# RPi-Display_Bplus_v11.net
KiCad netlist of a schematic drawn in EAGLE
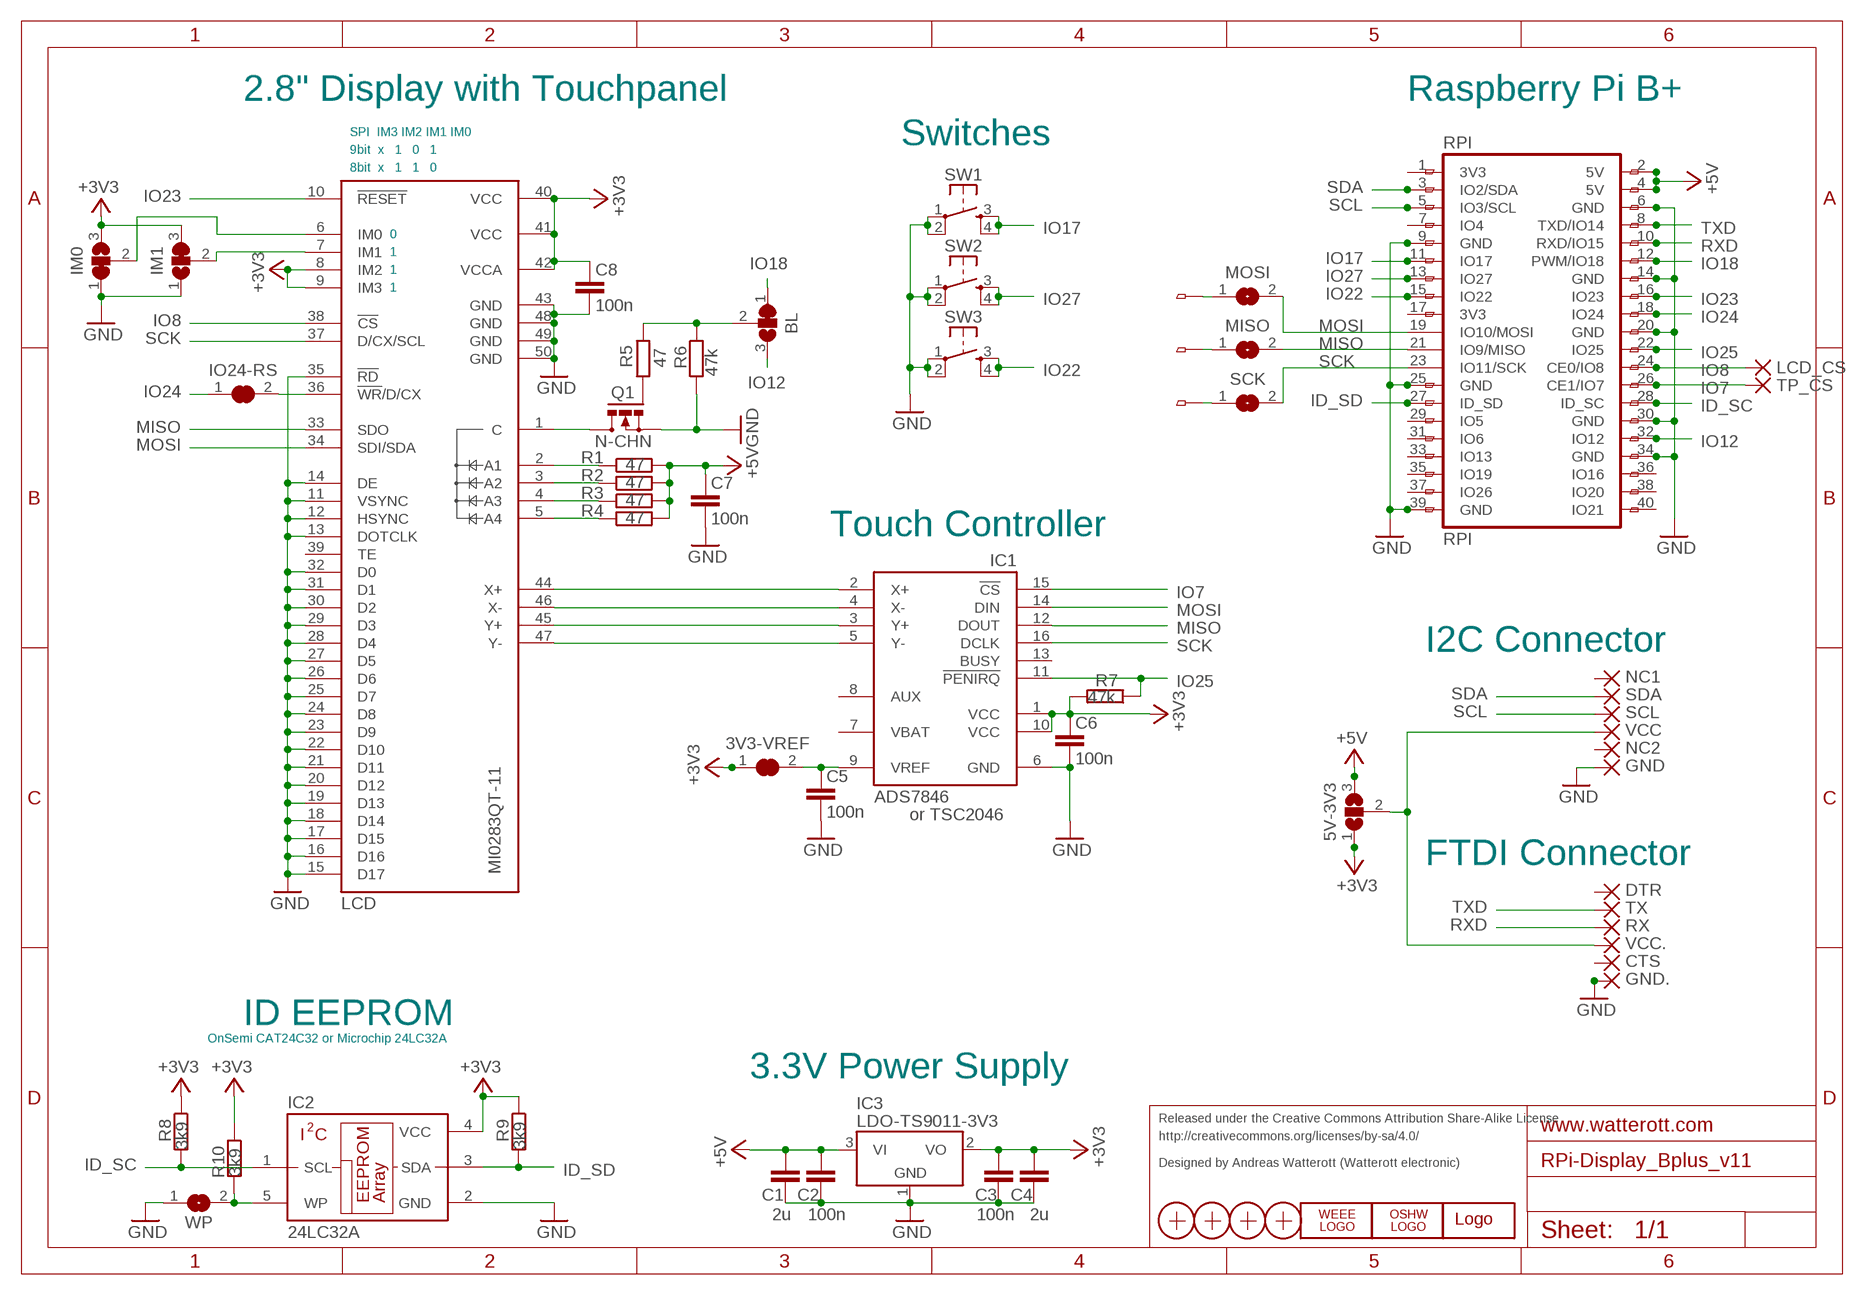
[diagram p0: schematic, sheet 1]

(export (version "E")
  (design (tool "Eeschema 10.0.6"))
  (components
    (comp (ref "3V3-VREF")
      (value "JUMPER2-NOCREAM")
      (footprint "eagle-import:JUMPER2_NC")
      (libsource (lib "eagle-import") (part "JUMPER2-NOCREAM"))
    )
    (comp (ref "5V-3V3")
      (value "JUMPER3-NOCREAM")
      (footprint "eagle-import:JUMPER3_NC")
      (libsource (lib "eagle-import") (part "JUMPER3-NOCREAM"))
    )
    (comp (ref "BL")
      (value "JUMPER3-NOCREAM")
      (footprint "eagle-import:JUMPER3_NC")
      (libsource (lib "eagle-import") (part "JUMPER3-NOCREAM"))
    )
    (comp (ref "C1")
      (value "2u")
      (footprint "eagle-import:C0603")
      (libsource (lib "eagle-import") (part "C-EUC0603"))
    )
    (comp (ref "C2")
      (value "100n")
      (footprint "eagle-import:C0603")
      (libsource (lib "eagle-import") (part "C-EUC0603"))
    )
    (comp (ref "C3")
      (value "100n")
      (footprint "eagle-import:C0603")
      (libsource (lib "eagle-import") (part "C-EUC0603"))
    )
    (comp (ref "C4")
      (value "2u")
      (footprint "eagle-import:C0603")
      (libsource (lib "eagle-import") (part "C-EUC0603"))
    )
    (comp (ref "C5")
      (value "100n")
      (footprint "eagle-import:C0603")
      (libsource (lib "eagle-import") (part "C-EUC0603"))
    )
    (comp (ref "C6")
      (value "100n")
      (footprint "eagle-import:C0603")
      (libsource (lib "eagle-import") (part "C-EUC0603"))
    )
    (comp (ref "C7")
      (value "100n")
      (footprint "eagle-import:C0603")
      (libsource (lib "eagle-import") (part "C-EUC0603"))
    )
    (comp (ref "C8")
      (value "100n")
      (footprint "eagle-import:C0603")
      (libsource (lib "eagle-import") (part "C-EUC0603"))
    )
    (comp (ref "CTS")
      (value "PAD-1.27X2.54_NC")
      (footprint "eagle-import:PAD-1.27X2.54_NC")
      (libsource (lib "eagle-import") (part "PAD-1.27X2.54_NC"))
    )
    (comp (ref "DTR")
      (value "PAD-1.27X2.54_NC")
      (footprint "eagle-import:PAD-1.27X2.54_NC")
      (libsource (lib "eagle-import") (part "PAD-1.27X2.54_NC"))
    )
    (comp (ref "GND")
      (value "PAD-1.27X2.54_NC")
      (footprint "eagle-import:PAD-1.27X2.54_NC")
      (libsource (lib "eagle-import") (part "PAD-1.27X2.54_NC"))
    )
    (comp (ref "GND.")
      (value "PAD-1.27X2.54_NC")
      (footprint "eagle-import:PAD-1.27X2.54_NC")
      (libsource (lib "eagle-import") (part "PAD-1.27X2.54_NC"))
    )
    (comp (ref "GPIO")
      (value "FH12-40S-0.5SH")
      (footprint "eagle-import:FH12-40S-0.5SH")
      (fields (field (name "MPN") "FH12-40S-0.5SH(55)"))
      (libsource (lib "eagle-import") (part "FH12-40S-0.5SH"))
    )
    (comp (ref "IC1")
      (value "ADS7846")
      (footprint "eagle-import:SSOP16")
      (libsource (lib "eagle-import") (part "ADS7846"))
    )
    (comp (ref "IC2")
      (value "24LC32A")
      (footprint "eagle-import:SOT23-5")
      (libsource (lib "eagle-import") (part "I2C_EEPROM-CAT24AA0X"))
    )
    (comp (ref "IC3")
      (value "LDO-TS9011-3V3")
      (footprint "eagle-import:SOT23")
      (libsource (lib "eagle-import") (part "LDO-TS9011-3V3"))
    )
    (comp (ref "IM0")
      (value "JUMPER3-NOCREAM")
      (footprint "eagle-import:JUMPER3_NC")
      (libsource (lib "eagle-import") (part "JUMPER3-NOCREAM"))
    )
    (comp (ref "IM1")
      (value "JUMPER3-NOCREAM")
      (footprint "eagle-import:JUMPER3_NC")
      (libsource (lib "eagle-import") (part "JUMPER3-NOCREAM"))
    )
    (comp (ref "IO24-RS")
      (value "JUMPER2-NOCREAM")
      (footprint "eagle-import:JUMPER2_NC")
      (libsource (lib "eagle-import") (part "JUMPER2-NOCREAM"))
    )
    (comp (ref "LCD")
      (value "MI0283QT-11")
      (footprint "eagle-import:MI0283QT11")
      (libsource (lib "eagle-import") (part "MI0283QT-11"))
    )
    (comp (ref "LCD_CS")
      (value "PAD-1.0_NC")
      (footprint "eagle-import:PAD-1.0_NC")
      (libsource (lib "eagle-import") (part "PAD-1.0_NC"))
    )
    (comp (ref "LOGO1")
      (value "OSHW_LOGO_6MILX0150-NT")
      (footprint "eagle-import:OSHW_6X150_NOTEXT")
      (libsource (lib "eagle-import") (part "OSHW_LOGO_6MILX0150-NT"))
    )
    (comp (ref "LOGO2")
      (value "WEEE_LOGO")
      (footprint "eagle-import:WEEE")
      (libsource (lib "eagle-import") (part "WEEE_LOGO"))
    )
    (comp (ref "MISO")
      (value "JUMPER2-NOCREAM")
      (footprint "eagle-import:JUMPER2_NC")
      (libsource (lib "eagle-import") (part "JUMPER2-NOCREAM"))
    )
    (comp (ref "MOSI")
      (value "JUMPER2-NOCREAM")
      (footprint "eagle-import:JUMPER2_NC")
      (libsource (lib "eagle-import") (part "JUMPER2-NOCREAM"))
    )
    (comp (ref "NC1")
      (value "PAD-1.27X2.54_NC")
      (footprint "eagle-import:PAD-1.27X2.54_NC")
      (libsource (lib "eagle-import") (part "PAD-1.27X2.54_NC"))
    )
    (comp (ref "NC2")
      (value "PAD-1.27X2.54_NC")
      (footprint "eagle-import:PAD-1.27X2.54_NC")
      (libsource (lib "eagle-import") (part "PAD-1.27X2.54_NC"))
    )
    (comp (ref "Q1")
      (value "N-CHN")
      (footprint "eagle-import:MICRO3")
      (libsource (lib "eagle-import") (part "IRLML2502"))
    )
    (comp (ref "R1")
      (value "47")
      (footprint "eagle-import:R0603")
      (libsource (lib "eagle-import") (part "R-EU_R0603"))
    )
    (comp (ref "R2")
      (value "47")
      (footprint "eagle-import:R0603")
      (libsource (lib "eagle-import") (part "R-EU_R0603"))
    )
    (comp (ref "R3")
      (value "47")
      (footprint "eagle-import:R0603")
      (libsource (lib "eagle-import") (part "R-EU_R0603"))
    )
    (comp (ref "R4")
      (value "47")
      (footprint "eagle-import:R0603")
      (libsource (lib "eagle-import") (part "R-EU_R0603"))
    )
    (comp (ref "R5")
      (value "47")
      (footprint "eagle-import:R0603")
      (libsource (lib "eagle-import") (part "R-EU_R0603"))
    )
    (comp (ref "R6")
      (value "47k")
      (footprint "eagle-import:R0603")
      (libsource (lib "eagle-import") (part "R-EU_R0603"))
    )
    (comp (ref "R7")
      (value "47k")
      (footprint "eagle-import:R0603")
      (libsource (lib "eagle-import") (part "R-EU_R0603"))
    )
    (comp (ref "R8")
      (value "3k9")
      (footprint "eagle-import:R0603")
      (libsource (lib "eagle-import") (part "R-EU_R0603"))
    )
    (comp (ref "R9")
      (value "3k9")
      (footprint "eagle-import:R0603")
      (libsource (lib "eagle-import") (part "R-EU_R0603"))
    )
    (comp (ref "R10")
      (value "3k9")
      (footprint "eagle-import:R0603")
      (libsource (lib "eagle-import") (part "R-EU_R0603"))
    )
    (comp (ref "RPI")
      (value "RPI")
      (footprint "eagle-import:RPI_B+")
      (libsource (lib "eagle-import") (part "RPI_B+"))
    )
    (comp (ref "RX")
      (value "PAD-1.27X2.54_NC")
      (footprint "eagle-import:PAD-1.27X2.54_NC")
      (libsource (lib "eagle-import") (part "PAD-1.27X2.54_NC"))
    )
    (comp (ref "SCK")
      (value "JUMPER2-NOCREAM")
      (footprint "eagle-import:JUMPER2_NC")
      (libsource (lib "eagle-import") (part "JUMPER2-NOCREAM"))
    )
    (comp (ref "SCL")
      (value "PAD-1.27X2.54_NC")
      (footprint "eagle-import:PAD-1.27X2.54_NC")
      (libsource (lib "eagle-import") (part "PAD-1.27X2.54_NC"))
    )
    (comp (ref "SDA")
      (value "PAD-1.27X2.54_NC")
      (footprint "eagle-import:PAD-1.27X2.54_NC")
      (libsource (lib "eagle-import") (part "PAD-1.27X2.54_NC"))
    )
    (comp (ref "SW1")
      (value "SWITCH-PTS840P")
      (footprint "eagle-import:SW_PTS840P")
      (libsource (lib "eagle-import") (part "SWITCH-PTS840P"))
    )
    (comp (ref "SW2")
      (value "SWITCH-PTS840P")
      (footprint "eagle-import:SW_PTS840P")
      (libsource (lib "eagle-import") (part "SWITCH-PTS840P"))
    )
    (comp (ref "SW3")
      (value "SWITCH-PTS840P")
      (footprint "eagle-import:SW_PTS840P")
      (libsource (lib "eagle-import") (part "SWITCH-PTS840P"))
    )
    (comp (ref "TP_CS")
      (value "PAD-1.0_NC")
      (footprint "eagle-import:PAD-1.0_NC")
      (libsource (lib "eagle-import") (part "PAD-1.0_NC"))
    )
    (comp (ref "TX")
      (value "PAD-1.27X2.54_NC")
      (footprint "eagle-import:PAD-1.27X2.54_NC")
      (libsource (lib "eagle-import") (part "PAD-1.27X2.54_NC"))
    )
    (comp (ref "U$1")
      (value "WE-LOGO")
      (footprint "eagle-import:WE-LOGO")
      (libsource (lib "eagle-import") (part "WE-LOGOPLACE"))
    )
    (comp (ref "VCC")
      (value "PAD-1.27X2.54_NC")
      (footprint "eagle-import:PAD-1.27X2.54_NC")
      (libsource (lib "eagle-import") (part "PAD-1.27X2.54_NC"))
    )
    (comp (ref "VCC.")
      (value "PAD-1.27X2.54_NC")
      (footprint "eagle-import:PAD-1.27X2.54_NC")
      (libsource (lib "eagle-import") (part "PAD-1.27X2.54_NC"))
    )
    (comp (ref "WP")
      (value "JUMPER2-NOCREAM")
      (footprint "eagle-import:JUMPER2_NC")
      (libsource (lib "eagle-import") (part "JUMPER2-NOCREAM"))
    )
    (comp (ref "X1")
      (value "PASSER")
      (footprint "eagle-import:PASSER")
      (libsource (lib "eagle-import") (part "PASSER"))
    )
    (comp (ref "X2")
      (value "PASSER")
      (footprint "eagle-import:PASSER")
      (libsource (lib "eagle-import") (part "PASSER"))
    )
    (comp (ref "X3")
      (value "PASSER")
      (footprint "eagle-import:PASSER")
      (libsource (lib "eagle-import") (part "PASSER"))
    )
    (comp (ref "X4")
      (value "PASSER")
      (footprint "eagle-import:PASSER")
      (libsource (lib "eagle-import") (part "PASSER"))
    )
  )
  (nets
    (net (code "1") (name "+3V3") (class "Default")
      (node (ref "3V3-VREF") (pin "1") (pinfunction "1_1") (pintype "passive"))
      (node (ref "5V-3V3") (pin "1") (pinfunction "1_1") (pintype "passive"))
      (node (ref "C3") (pin "1") (pinfunction "1_1") (pintype "passive"))
      (node (ref "C4") (pin "1") (pinfunction "1_1") (pintype "passive"))
      (node (ref "C6") (pin "1") (pinfunction "1_1") (pintype "passive"))
      (node (ref "C8") (pin "1") (pinfunction "1_1") (pintype "passive"))
      (node (ref "IC1") (pin "1") (pinfunction "VCC_1") (pintype "power_in"))
      (node (ref "IC1") (pin "10") (pinfunction "VCC_10") (pintype "power_in"))
      (node (ref "IC2") (pin "4") (pinfunction "VCC_4") (pintype "power_in"))
      (node (ref "IC3") (pin "2") (pinfunction "VO_2") (pintype "passive"))
      (node (ref "IM0") (pin "3") (pinfunction "3_3") (pintype "passive"))
      (node (ref "IM1") (pin "3") (pinfunction "3_3") (pintype "passive"))
      (node (ref "LCD") (pin "40") (pinfunction "VCC_40") (pintype "power_in"))
      (node (ref "LCD") (pin "41") (pinfunction "VCC_41") (pintype "power_in"))
      (node (ref "LCD") (pin "42") (pinfunction "VCCA_42") (pintype "power_in"))
      (node (ref "LCD") (pin "8") (pinfunction "IM2_8") (pintype "input"))
      (node (ref "LCD") (pin "9") (pinfunction "IM3_9") (pintype "input"))
      (node (ref "R10") (pin "1") (pinfunction "1_1") (pintype "passive"))
      (node (ref "R7") (pin "2") (pinfunction "2_2") (pintype "passive"))
      (node (ref "R8") (pin "1") (pinfunction "1_1") (pintype "passive"))
      (node (ref "R9") (pin "1") (pinfunction "1_1") (pintype "passive"))
    )
    (net (code "2") (name "+5V") (class "Default")
      (node (ref "5V-3V3") (pin "3") (pinfunction "3_3") (pintype "passive"))
      (node (ref "C1") (pin "1") (pinfunction "1_1") (pintype "passive"))
      (node (ref "C2") (pin "1") (pinfunction "1_1") (pintype "passive"))
      (node (ref "C7") (pin "1") (pinfunction "1_1") (pintype "passive"))
      (node (ref "GPIO") (pin "37") (pinfunction "1_37") (pintype "passive"))
      (node (ref "GPIO") (pin "39") (pinfunction "1_39") (pintype "passive"))
      (node (ref "IC3") (pin "3") (pinfunction "VI_3") (pintype "input"))
      (node (ref "R1") (pin "2") (pinfunction "2_2") (pintype "passive"))
      (node (ref "R2") (pin "2") (pinfunction "2_2") (pintype "passive"))
      (node (ref "R3") (pin "2") (pinfunction "2_2") (pintype "passive"))
      (node (ref "R4") (pin "2") (pinfunction "2_2") (pintype "passive"))
      (node (ref "RPI") (pin "2") (pinfunction "5V_2") (pintype "passive"))
      (node (ref "RPI") (pin "4") (pinfunction "5V_4") (pintype "passive"))
    )
    (net (code "3") (name "/ID_SC") (class "Default")
      (node (ref "GPIO") (pin "13") (pinfunction "1_13") (pintype "passive"))
      (node (ref "IC2") (pin "1") (pinfunction "SCL_1") (pintype "bidirectional"))
      (node (ref "R8") (pin "2") (pinfunction "2_2") (pintype "passive"))
      (node (ref "RPI") (pin "28") (pinfunction "ID_SC_28") (pintype "bidirectional"))
    )
    (net (code "4") (name "/ID_SD") (class "Default")
      (node (ref "GPIO") (pin "14") (pinfunction "1_14") (pintype "passive"))
      (node (ref "IC2") (pin "3") (pinfunction "SDA_3") (pintype "bidirectional"))
      (node (ref "R9") (pin "2") (pinfunction "2_2") (pintype "passive"))
      (node (ref "RPI") (pin "27") (pinfunction "ID_SD_27") (pintype "bidirectional"))
    )
    (net (code "5") (name "/IO7") (class "Default")
      (node (ref "GPIO") (pin "15") (pinfunction "1_15") (pintype "passive"))
      (node (ref "IC1") (pin "15") (pinfunction "~{CS}_15") (pintype "input"))
      (node (ref "RPI") (pin "26") (pinfunction "CE1/IO7_26") (pintype "passive"))
      (node (ref "TP_CS") (pin "1") (pinfunction "P_1") (pintype "passive"))
    )
    (net (code "6") (name "/IO8") (class "Default")
      (node (ref "GPIO") (pin "17") (pinfunction "1_17") (pintype "passive"))
      (node (ref "LCD") (pin "38") (pinfunction "~{CS}_38") (pintype "input"))
      (node (ref "LCD_CS") (pin "1") (pinfunction "P_1") (pintype "passive"))
      (node (ref "RPI") (pin "24") (pinfunction "CE0/IO8_24") (pintype "passive"))
    )
    (net (code "7") (name "/IO12") (class "Default")
      (node (ref "BL") (pin "3") (pinfunction "3_3") (pintype "passive"))
      (node (ref "GPIO") (pin "9") (pinfunction "1_9") (pintype "passive"))
      (node (ref "RPI") (pin "32") (pinfunction "IO12_32") (pintype "bidirectional"))
    )
    (net (code "8") (name "/IO17") (class "Default")
      (node (ref "GPIO") (pin "30") (pinfunction "1_30") (pintype "passive"))
      (node (ref "RPI") (pin "11") (pinfunction "IO17_11") (pintype "passive"))
      (node (ref "SW1") (pin "3") (pinfunction "S_3") (pintype "passive"))
      (node (ref "SW1") (pin "4") (pinfunction "S1_4") (pintype "passive"))
    )
    (net (code "9") (name "/IO18") (class "Default")
      (node (ref "BL") (pin "1") (pinfunction "1_1") (pintype "passive"))
      (node (ref "GPIO") (pin "29") (pinfunction "1_29") (pintype "passive"))
      (node (ref "RPI") (pin "12") (pinfunction "PWM/IO18_12") (pintype "passive"))
    )
    (net (code "10") (name "/IO22") (class "Default")
      (node (ref "GPIO") (pin "26") (pinfunction "1_26") (pintype "passive"))
      (node (ref "RPI") (pin "15") (pinfunction "IO22_15") (pintype "passive"))
      (node (ref "SW3") (pin "3") (pinfunction "S_3") (pintype "passive"))
      (node (ref "SW3") (pin "4") (pinfunction "S1_4") (pintype "passive"))
    )
    (net (code "11") (name "/IO23") (class "Default")
      (node (ref "GPIO") (pin "25") (pinfunction "1_25") (pintype "passive"))
      (node (ref "LCD") (pin "10") (pinfunction "~{RESET}_10") (pintype "input"))
      (node (ref "RPI") (pin "16") (pinfunction "IO23_16") (pintype "passive"))
    )
    (net (code "12") (name "/IO24") (class "Default")
      (node (ref "GPIO") (pin "23") (pinfunction "1_23") (pintype "passive"))
      (node (ref "IO24-RS") (pin "1") (pinfunction "1_1") (pintype "passive"))
      (node (ref "RPI") (pin "18") (pinfunction "IO24_18") (pintype "passive"))
    )
    (net (code "13") (name "/IO25") (class "Default")
      (node (ref "GPIO") (pin "19") (pinfunction "1_19") (pintype "passive"))
      (node (ref "IC1") (pin "11") (pinfunction "~{PENIRQ}_11") (pintype "output"))
      (node (ref "R7") (pin "1") (pinfunction "1_1") (pintype "passive"))
      (node (ref "RPI") (pin "22") (pinfunction "IO25_22") (pintype "passive"))
    )
    (net (code "14") (name "/IO27") (class "Default")
      (node (ref "GPIO") (pin "28") (pinfunction "1_28") (pintype "passive"))
      (node (ref "RPI") (pin "13") (pinfunction "IO27_13") (pintype "passive"))
      (node (ref "SW2") (pin "3") (pinfunction "S_3") (pintype "passive"))
      (node (ref "SW2") (pin "4") (pinfunction "S1_4") (pintype "passive"))
    )
    (net (code "15") (name "/MISO") (class "Default")
      (node (ref "IC1") (pin "12") (pinfunction "DOUT_12") (pintype "input"))
      (node (ref "LCD") (pin "33") (pinfunction "SDO_33") (pintype "output"))
      (node (ref "MISO") (pin "2") (pinfunction "2_2") (pintype "passive"))
      (node (ref "RPI") (pin "21") (pinfunction "IO9/MISO_21") (pintype "passive"))
    )
    (net (code "16") (name "/MOSI") (class "Default")
      (node (ref "IC1") (pin "14") (pinfunction "DIN_14") (pintype "input"))
      (node (ref "LCD") (pin "34") (pinfunction "SDI/SDA_34") (pintype "input"))
      (node (ref "MOSI") (pin "2") (pinfunction "2_2") (pintype "passive"))
      (node (ref "RPI") (pin "19") (pinfunction "IO10/MOSI_19") (pintype "passive"))
    )
    (net (code "17") (name "/RXD") (class "Default")
      (node (ref "GPIO") (pin "31") (pinfunction "1_31") (pintype "passive"))
      (node (ref "RPI") (pin "10") (pinfunction "RXD/IO15_10") (pintype "passive"))
      (node (ref "RX") (pin "1") (pinfunction "P_1") (pintype "passive"))
    )
    (net (code "18") (name "/SCK") (class "Default")
      (node (ref "IC1") (pin "16") (pinfunction "DCLK_16") (pintype "output"))
      (node (ref "LCD") (pin "37") (pinfunction "D/CX/SCL_37") (pintype "input"))
      (node (ref "RPI") (pin "23") (pinfunction "IO11/SCK_23") (pintype "passive"))
      (node (ref "SCK") (pin "2") (pinfunction "2_2") (pintype "passive"))
    )
    (net (code "19") (name "/SCL") (class "Default")
      (node (ref "GPIO") (pin "36") (pinfunction "1_36") (pintype "passive"))
      (node (ref "RPI") (pin "5") (pinfunction "IO3/SCL_5") (pintype "passive"))
      (node (ref "SCL") (pin "1") (pinfunction "P_1") (pintype "passive"))
    )
    (net (code "20") (name "/SDA") (class "Default")
      (node (ref "GPIO") (pin "38") (pinfunction "1_38") (pintype "passive"))
      (node (ref "RPI") (pin "3") (pinfunction "IO2/SDA_3") (pintype "passive"))
      (node (ref "SDA") (pin "1") (pinfunction "P_1") (pintype "passive"))
    )
    (net (code "21") (name "/TXD") (class "Default")
      (node (ref "GPIO") (pin "33") (pinfunction "1_33") (pintype "passive"))
      (node (ref "RPI") (pin "8") (pinfunction "TXD/IO14_8") (pintype "passive"))
      (node (ref "TX") (pin "1") (pinfunction "P_1") (pintype "passive"))
    )
    (net (code "22") (name "GND") (class "Default")
      (node (ref "C1") (pin "2") (pinfunction "2_2") (pintype "passive"))
      (node (ref "C2") (pin "2") (pinfunction "2_2") (pintype "passive"))
      (node (ref "C3") (pin "2") (pinfunction "2_2") (pintype "passive"))
      (node (ref "C4") (pin "2") (pinfunction "2_2") (pintype "passive"))
      (node (ref "C5") (pin "2") (pinfunction "2_2") (pintype "passive"))
      (node (ref "C6") (pin "2") (pinfunction "2_2") (pintype "passive"))
      (node (ref "C7") (pin "2") (pinfunction "2_2") (pintype "passive"))
      (node (ref "C8") (pin "2") (pinfunction "2_2") (pintype "passive"))
      (node (ref "GND") (pin "1") (pinfunction "P_1") (pintype "passive"))
      (node (ref "GND.") (pin "1") (pinfunction "P_1") (pintype "passive"))
      (node (ref "GPIO") (pin "11") (pinfunction "1_11") (pintype "passive"))
      (node (ref "GPIO") (pin "16") (pinfunction "1_16") (pintype "passive"))
      (node (ref "GPIO") (pin "2") (pinfunction "1_2") (pintype "passive"))
      (node (ref "GPIO") (pin "21") (pinfunction "1_21") (pintype "passive"))
      (node (ref "GPIO") (pin "27") (pinfunction "1_27") (pintype "passive"))
      (node (ref "GPIO") (pin "32") (pinfunction "1_32") (pintype "passive"))
      (node (ref "GPIO") (pin "35") (pinfunction "1_35") (pintype "passive"))
      (node (ref "GPIO") (pin "7") (pinfunction "1_7") (pintype "passive"))
      (node (ref "IC1") (pin "6") (pinfunction "GND_6") (pintype "power_in"))
      (node (ref "IC2") (pin "2") (pinfunction "GND_2") (pintype "power_in"))
      (node (ref "IC3") (pin "1") (pinfunction "GND_1") (pintype "passive"))
      (node (ref "IM0") (pin "1") (pinfunction "1_1") (pintype "passive"))
      (node (ref "IM1") (pin "1") (pinfunction "1_1") (pintype "passive"))
      (node (ref "LCD") (pin "11") (pinfunction "VSYNC_11") (pintype "input"))
      (node (ref "LCD") (pin "12") (pinfunction "HSYNC_12") (pintype "input"))
      (node (ref "LCD") (pin "13") (pinfunction "DOTCLK_13") (pintype "input"))
      (node (ref "LCD") (pin "14") (pinfunction "DE_14") (pintype "input"))
      (node (ref "LCD") (pin "15") (pinfunction "D17_15") (pintype "input"))
      (node (ref "LCD") (pin "16") (pinfunction "D16_16") (pintype "input"))
      (node (ref "LCD") (pin "17") (pinfunction "D15_17") (pintype "input"))
      (node (ref "LCD") (pin "18") (pinfunction "D14_18") (pintype "input"))
      (node (ref "LCD") (pin "19") (pinfunction "D13_19") (pintype "input"))
      (node (ref "LCD") (pin "20") (pinfunction "D12_20") (pintype "input"))
      (node (ref "LCD") (pin "21") (pinfunction "D11_21") (pintype "input"))
      (node (ref "LCD") (pin "22") (pinfunction "D10_22") (pintype "input"))
      (node (ref "LCD") (pin "23") (pinfunction "D9_23") (pintype "input"))
      (node (ref "LCD") (pin "24") (pinfunction "D8_24") (pintype "input"))
      (node (ref "LCD") (pin "25") (pinfunction "D7_25") (pintype "input"))
      (node (ref "LCD") (pin "26") (pinfunction "D6_26") (pintype "input"))
      (node (ref "LCD") (pin "27") (pinfunction "D5_27") (pintype "input"))
      (node (ref "LCD") (pin "28") (pinfunction "D4_28") (pintype "input"))
      (node (ref "LCD") (pin "29") (pinfunction "D3_29") (pintype "input"))
      (node (ref "LCD") (pin "30") (pinfunction "D2_30") (pintype "input"))
      (node (ref "LCD") (pin "31") (pinfunction "D1_31") (pintype "input"))
      (node (ref "LCD") (pin "32") (pinfunction "D0_32") (pintype "input"))
      (node (ref "LCD") (pin "35") (pinfunction "~{RD}_35") (pintype "input"))
      (node (ref "LCD") (pin "43") (pinfunction "GND_43") (pintype "power_in"))
      (node (ref "LCD") (pin "48") (pinfunction "GND_48") (pintype "power_in"))
      (node (ref "LCD") (pin "49") (pinfunction "GND_49") (pintype "power_in"))
      (node (ref "LCD") (pin "50") (pinfunction "GND_50") (pintype "power_in"))
      (node (ref "Q1") (pin "2") (pinfunction "S_2") (pintype "passive"))
      (node (ref "R6") (pin "2") (pinfunction "2_2") (pintype "passive"))
      (node (ref "RPI") (pin "14") (pinfunction "GND_14") (pintype "passive"))
      (node (ref "RPI") (pin "20") (pinfunction "GND_20") (pintype "passive"))
      (node (ref "RPI") (pin "25") (pinfunction "GND_25") (pintype "passive"))
      (node (ref "RPI") (pin "30") (pinfunction "GND_30") (pintype "bidirectional"))
      (node (ref "RPI") (pin "34") (pinfunction "GND_34") (pintype "bidirectional"))
      (node (ref "RPI") (pin "39") (pinfunction "GND_39") (pintype "bidirectional"))
      (node (ref "RPI") (pin "6") (pinfunction "GND_6") (pintype "passive"))
      (node (ref "RPI") (pin "9") (pinfunction "GND_9") (pintype "passive"))
      (node (ref "SW1") (pin "1") (pinfunction "P_1") (pintype "passive"))
      (node (ref "SW1") (pin "2") (pinfunction "P1_2") (pintype "passive"))
      (node (ref "SW2") (pin "1") (pinfunction "P_1") (pintype "passive"))
      (node (ref "SW2") (pin "2") (pinfunction "P1_2") (pintype "passive"))
      (node (ref "SW3") (pin "1") (pinfunction "P_1") (pintype "passive"))
      (node (ref "SW3") (pin "2") (pinfunction "P1_2") (pintype "passive"))
      (node (ref "WP") (pin "1") (pinfunction "1_1") (pintype "passive"))
    )
    (net (code "23") (name "Net-(BL-Pad2)") (class "Default")
      (node (ref "BL") (pin "2") (pinfunction "2_2") (pintype "passive"))
      (node (ref "R5") (pin "2") (pinfunction "2_2") (pintype "passive"))
      (node (ref "R6") (pin "1") (pinfunction "1_1") (pintype "passive"))
    )
    (net (code "24") (name "Net-(GPIOAB-1)") (class "Default")
      (node (ref "GPIO") (pin "34") (pinfunction "1_34") (pintype "passive"))
      (node (ref "RPI") (pin "7") (pinfunction "IO4_7") (pintype "passive"))
    )
    (net (code "25") (name "Net-(GPIOAH-1)") (class "Default")
      (node (ref "GPIO") (pin "4") (pinfunction "1_4") (pintype "passive"))
      (node (ref "RPI") (pin "37") (pinfunction "IO26_37") (pintype "bidirectional"))
    )
    (net (code "26") (name "Net-(GPIOAI-1)") (class "Default")
      (node (ref "GPIO") (pin "40") (pinfunction "1_40") (pintype "passive"))
      (node (ref "RPI") (pin "1") (pinfunction "3V3_1") (pintype "passive"))
    )
    (net (code "27") (name "Net-(GPIOAJ-1)") (class "Default")
      (node (ref "GPIO") (pin "5") (pinfunction "1_5") (pintype "passive"))
      (node (ref "RPI") (pin "36") (pinfunction "IO16_36") (pintype "bidirectional"))
    )
    (net (code "28") (name "Net-(GPIOAK-1)") (class "Default")
      (node (ref "GPIO") (pin "6") (pinfunction "1_6") (pintype "passive"))
      (node (ref "RPI") (pin "35") (pinfunction "IO19_35") (pintype "bidirectional"))
    )
    (net (code "29") (name "Net-(GPIOAM-1)") (class "Default")
      (node (ref "GPIO") (pin "8") (pinfunction "1_8") (pintype "passive"))
      (node (ref "RPI") (pin "33") (pinfunction "IO13_33") (pintype "bidirectional"))
    )
    (net (code "30") (name "Net-(GPIOB-1)") (class "Default")
      (node (ref "GPIO") (pin "10") (pinfunction "1_10") (pintype "passive"))
      (node (ref "RPI") (pin "31") (pinfunction "IO6_31") (pintype "bidirectional"))
    )
    (net (code "31") (name "Net-(GPIOD-1)") (class "Default")
      (node (ref "GPIO") (pin "12") (pinfunction "1_12") (pintype "passive"))
      (node (ref "RPI") (pin "29") (pinfunction "IO5_29") (pintype "bidirectional"))
    )
    (net (code "32") (name "Net-(GPIOJ-1)") (class "Default")
      (node (ref "GPIO") (pin "18") (pinfunction "1_18") (pintype "passive"))
      (node (ref "SCK") (pin "1") (pinfunction "1_1") (pintype "passive"))
    )
    (net (code "33") (name "Net-(GPIOM-1)") (class "Default")
      (node (ref "GPIO") (pin "20") (pinfunction "1_20") (pintype "passive"))
      (node (ref "MISO") (pin "1") (pinfunction "1_1") (pintype "passive"))
    )
    (net (code "34") (name "Net-(GPIOO-1)") (class "Default")
      (node (ref "GPIO") (pin "22") (pinfunction "1_22") (pintype "passive"))
      (node (ref "MOSI") (pin "1") (pinfunction "1_1") (pintype "passive"))
    )
    (net (code "35") (name "Net-(GPIOQ-1)") (class "Default")
      (node (ref "GPIO") (pin "24") (pinfunction "1_24") (pintype "passive"))
      (node (ref "RPI") (pin "17") (pinfunction "3V3_17") (pintype "passive"))
    )
    (net (code "36") (name "Net-(GPIOW-1)") (class "Default")
      (node (ref "GPIO") (pin "3") (pinfunction "1_3") (pintype "passive"))
      (node (ref "RPI") (pin "38") (pinfunction "IO20_38") (pintype "bidirectional"))
    )
    (net (code "37") (name "Net-(IC1-VREF)") (class "Default")
      (node (ref "3V3-VREF") (pin "2") (pinfunction "2_2") (pintype "passive"))
      (node (ref "C5") (pin "1") (pinfunction "1_1") (pintype "passive"))
      (node (ref "IC1") (pin "9") (pinfunction "VREF_9") (pintype "bidirectional"))
    )
    (net (code "38") (name "Net-(IC1-X+)") (class "Default")
      (node (ref "IC1") (pin "2") (pinfunction "X+_2") (pintype "input"))
      (node (ref "LCD") (pin "44") (pinfunction "X+_44") (pintype "passive"))
    )
    (net (code "39") (name "Net-(IC1-X-)") (class "Default")
      (node (ref "IC1") (pin "4") (pinfunction "X-_4") (pintype "input"))
      (node (ref "LCD") (pin "46") (pinfunction "X-_46") (pintype "passive"))
    )
    (net (code "40") (name "Net-(IC1-Y+)") (class "Default")
      (node (ref "IC1") (pin "3") (pinfunction "Y+_3") (pintype "input"))
      (node (ref "LCD") (pin "45") (pinfunction "Y+_45") (pintype "passive"))
    )
    (net (code "41") (name "Net-(IC1-Y-)") (class "Default")
      (node (ref "IC1") (pin "5") (pinfunction "Y-_5") (pintype "input"))
      (node (ref "LCD") (pin "47") (pinfunction "Y-_47") (pintype "passive"))
    )
    (net (code "42") (name "Net-(IC2-WP)") (class "Default")
      (node (ref "IC2") (pin "5") (pinfunction "WP_5") (pintype "bidirectional"))
      (node (ref "R10") (pin "2") (pinfunction "2_2") (pintype "passive"))
      (node (ref "WP") (pin "2") (pinfunction "2_2") (pintype "passive"))
    )
    (net (code "43") (name "Net-(LCD-A1)") (class "Default")
      (node (ref "LCD") (pin "2") (pinfunction "A1_2") (pintype "power_in"))
      (node (ref "R1") (pin "1") (pinfunction "1_1") (pintype "passive"))
    )
    (net (code "44") (name "Net-(LCD-A2)") (class "Default")
      (node (ref "LCD") (pin "3") (pinfunction "A2_3") (pintype "power_in"))
      (node (ref "R2") (pin "1") (pinfunction "1_1") (pintype "passive"))
    )
    (net (code "45") (name "Net-(LCD-A3)") (class "Default")
      (node (ref "LCD") (pin "4") (pinfunction "A3_4") (pintype "power_in"))
      (node (ref "R3") (pin "1") (pinfunction "1_1") (pintype "passive"))
    )
    (net (code "46") (name "Net-(LCD-A4)") (class "Default")
      (node (ref "LCD") (pin "5") (pinfunction "A4_5") (pintype "power_in"))
      (node (ref "R4") (pin "1") (pinfunction "1_1") (pintype "passive"))
    )
    (net (code "47") (name "Net-(LCD-C)") (class "Default")
      (node (ref "LCD") (pin "1") (pinfunction "C_1") (pintype "power_in"))
      (node (ref "Q1") (pin "3") (pinfunction "D_3") (pintype "passive"))
    )
    (net (code "48") (name "Net-(LCD-IM0)") (class "Default")
      (node (ref "IM0") (pin "2") (pinfunction "2_2") (pintype "passive"))
      (node (ref "LCD") (pin "6") (pinfunction "IM0_6") (pintype "input"))
    )
    (net (code "49") (name "Net-(LCD-IM1)") (class "Default")
      (node (ref "IM1") (pin "2") (pinfunction "2_2") (pintype "passive"))
      (node (ref "LCD") (pin "7") (pinfunction "IM1_7") (pintype "input"))
    )
    (net (code "50") (name "Net-(LCD-~{WR}{slash}D{slash}CX)") (class "Default")
      (node (ref "IO24-RS") (pin "2") (pinfunction "2_2") (pintype "passive"))
      (node (ref "LCD") (pin "36") (pinfunction "~{WR}/D/CX_36") (pintype "input"))
    )
    (net (code "51") (name "Net-(Q1-G)") (class "Default")
      (node (ref "Q1") (pin "1") (pinfunction "G_1") (pintype "passive"))
      (node (ref "R5") (pin "1") (pinfunction "1_1") (pintype "passive"))
    )
    (net (code "52") (name "Net-(RPI-IO21)") (class "Default")
      (node (ref "GPIO") (pin "1") (pinfunction "1_1") (pintype "passive"))
      (node (ref "RPI") (pin "40") (pinfunction "IO21_40") (pintype "bidirectional"))
    )
    (net (code "53") (name "Net-(VCC-P)") (class "Default")
      (node (ref "5V-3V3") (pin "2") (pinfunction "2_2") (pintype "passive"))
      (node (ref "VCC") (pin "1") (pinfunction "P_1") (pintype "passive"))
      (node (ref "VCC.") (pin "1") (pinfunction "P_1") (pintype "passive"))
    )
    (net (code "54") (name "unconnected-(CTS-P-Pad1)") (class "Default")
      (node (ref "CTS") (pin "1") (pinfunction "P_1") (pintype "passive"))
    )
    (net (code "55") (name "unconnected-(DTR-P-Pad1)") (class "Default")
      (node (ref "DTR") (pin "1") (pinfunction "P_1") (pintype "passive"))
    )
    (net (code "56") (name "unconnected-(IC1-AUX-Pad8)") (class "Default")
      (node (ref "IC1") (pin "8") (pinfunction "AUX_8") (pintype "input"))
    )
    (net (code "57") (name "unconnected-(IC1-BUSY-Pad13)") (class "Default")
      (node (ref "IC1") (pin "13") (pinfunction "BUSY_13") (pintype "output"))
    )
    (net (code "58") (name "unconnected-(IC1-VBAT-Pad7)") (class "Default")
      (node (ref "IC1") (pin "7") (pinfunction "VBAT_7") (pintype "input"))
    )
    (net (code "59") (name "unconnected-(LCD-TE-Pad39)") (class "Default")
      (node (ref "LCD") (pin "39") (pinfunction "TE_39") (pintype "output"))
    )
    (net (code "60") (name "unconnected-(NC1-P-Pad1)") (class "Default")
      (node (ref "NC1") (pin "1") (pinfunction "P_1") (pintype "passive"))
    )
    (net (code "61") (name "unconnected-(NC2-P-Pad1)") (class "Default")
      (node (ref "NC2") (pin "1") (pinfunction "P_1") (pintype "passive"))
    )
  )
)
